# FuseBoardSchematic.net
KiCad netlist of a schematic drawn in Altium Designer
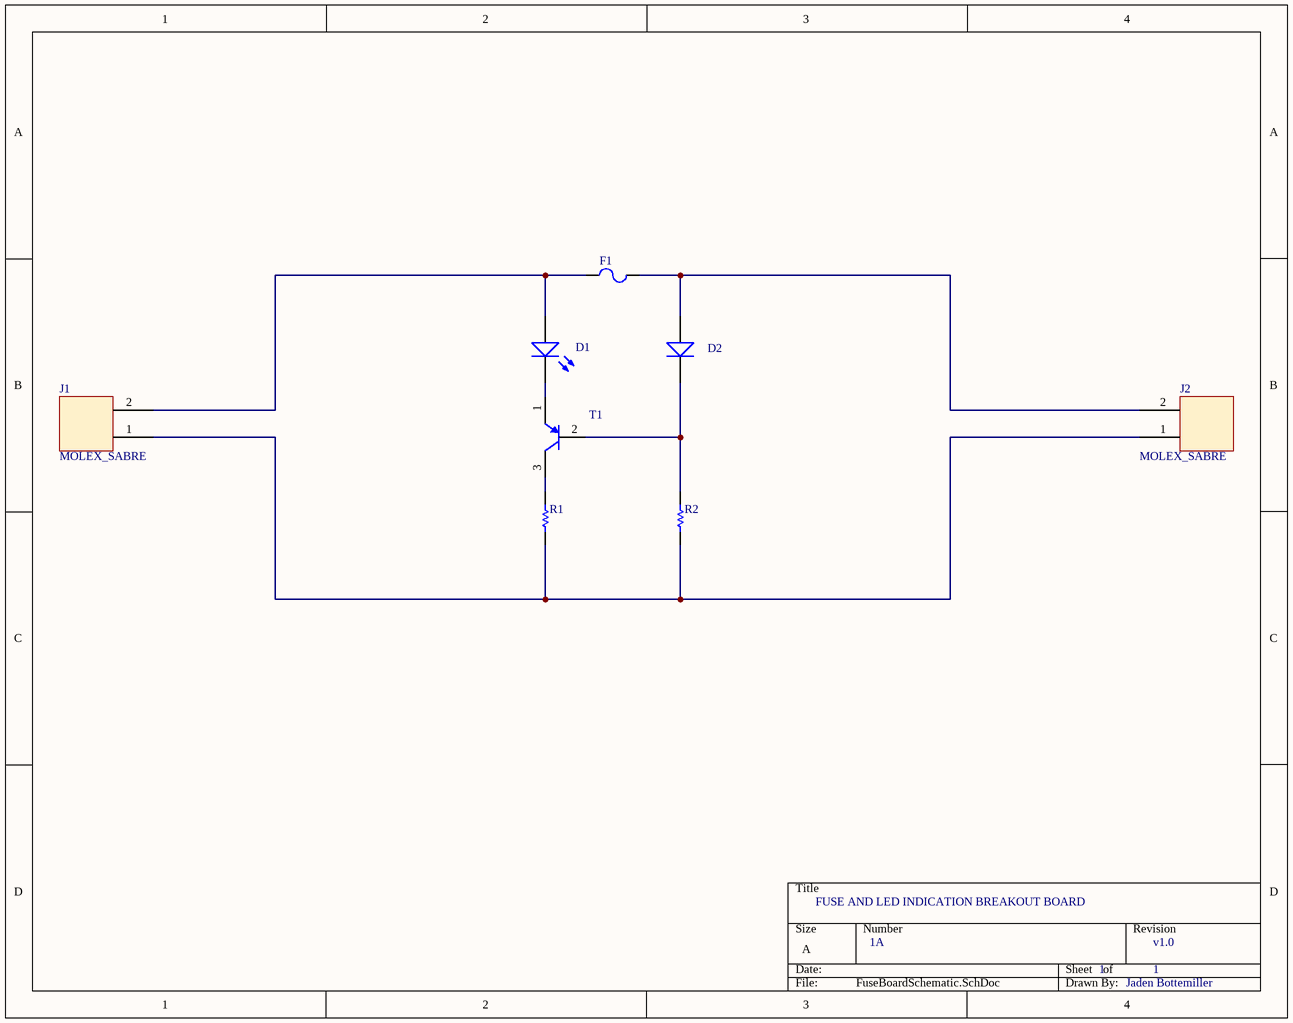
[diagram p0: FuseBoardSchematic.SchDoc]

(export (version "E")
  (design (tool "Eeschema 10.0.6"))
  (components
    (comp (ref "D1") (value "LED") (footprint "DIOC1608X08L") (libsource (lib "FuseBoard") (part "LED")))
    (comp (ref "D2") (value "DIODE") (footprint "DIOC5226X24L") (libsource (lib "FuseBoard") (part "DIODE")))
    (comp (ref "F1") (value "FUSE") (footprint "FUSE HOLDER") (libsource (lib "FuseBoard") (part "FUSE")))
    (comp (ref "J1")
      (value "MOLEX_SABRE")
      (footprint "1720420202")
      (libsource (lib "") (part "MOLEX_SABRE_1"))
    )
    (comp (ref "J2")
      (value "MOLEX_SABRE")
      (footprint "1720420202")
      (libsource (lib "FuseBoard") (part "MOLEX_SABRE"))
    )
    (comp (ref "R1") (value "RES") (footprint "RESC3115X06L") (libsource (lib "FuseBoard") (part "RES")))
    (comp (ref "R2") (value "RES") (footprint "RESC3115X06L") (libsource (lib "FuseBoard") (part "RES")))
    (comp (ref "T1") (value "PNP") (footprint "SOT100P240X110-3N") (libsource (lib "FuseBoard") (part "PNP")))
  )
  (nets
    (net (code "1") (name "Net-(D1-PadA)") (class "Default")
      (node (ref "D1") (pin "A") (pinfunction "A_A") (pintype "passive"))
      (node (ref "F1") (pin "1") (pinfunction "1_1") (pintype "passive"))
      (node (ref "J1") (pin "2") (pinfunction "Pin_2") (pintype "passive"))
    )
    (net (code "2") (name "Net-(D2-PadA)") (class "Default")
      (node (ref "D2") (pin "A") (pinfunction "A_A") (pintype "passive"))
      (node (ref "F1") (pin "2") (pinfunction "2_2") (pintype "passive"))
      (node (ref "J2") (pin "2") (pinfunction "Pin_2") (pintype "passive"))
    )
    (net (code "3") (name "Net-(J1-Pin-Pad1)") (class "Default")
      (node (ref "J1") (pin "1") (pinfunction "Pin_1") (pintype "passive"))
      (node (ref "J2") (pin "1") (pinfunction "Pin_1") (pintype "passive"))
      (node (ref "R1") (pin "2") (pinfunction "2_2") (pintype "passive"))
      (node (ref "R2") (pin "2") (pinfunction "2_2") (pintype "passive"))
    )
    (net (code "4") (name "Net-(T1-B1)") (class "Default")
      (node (ref "D2") (pin "C") (pinfunction "C_C") (pintype "passive"))
      (node (ref "R2") (pin "1") (pinfunction "1_1") (pintype "passive"))
      (node (ref "T1") (pin "2") (pinfunction "B1_2") (pintype "passive"))
    )
    (net (code "5") (name "Net-(T1-C1)") (class "Default")
      (node (ref "R1") (pin "1") (pinfunction "1_1") (pintype "passive"))
      (node (ref "T1") (pin "3") (pinfunction "C1_3") (pintype "passive"))
    )
    (net (code "6") (name "Net-(T1-E1)") (class "Default")
      (node (ref "D1") (pin "C") (pinfunction "C_C") (pintype "passive"))
      (node (ref "T1") (pin "1") (pinfunction "E1_1") (pintype "passive"))
    )
  )
)
